# led_brick.net
KiCad netlist of a schematic drawn in EAGLE
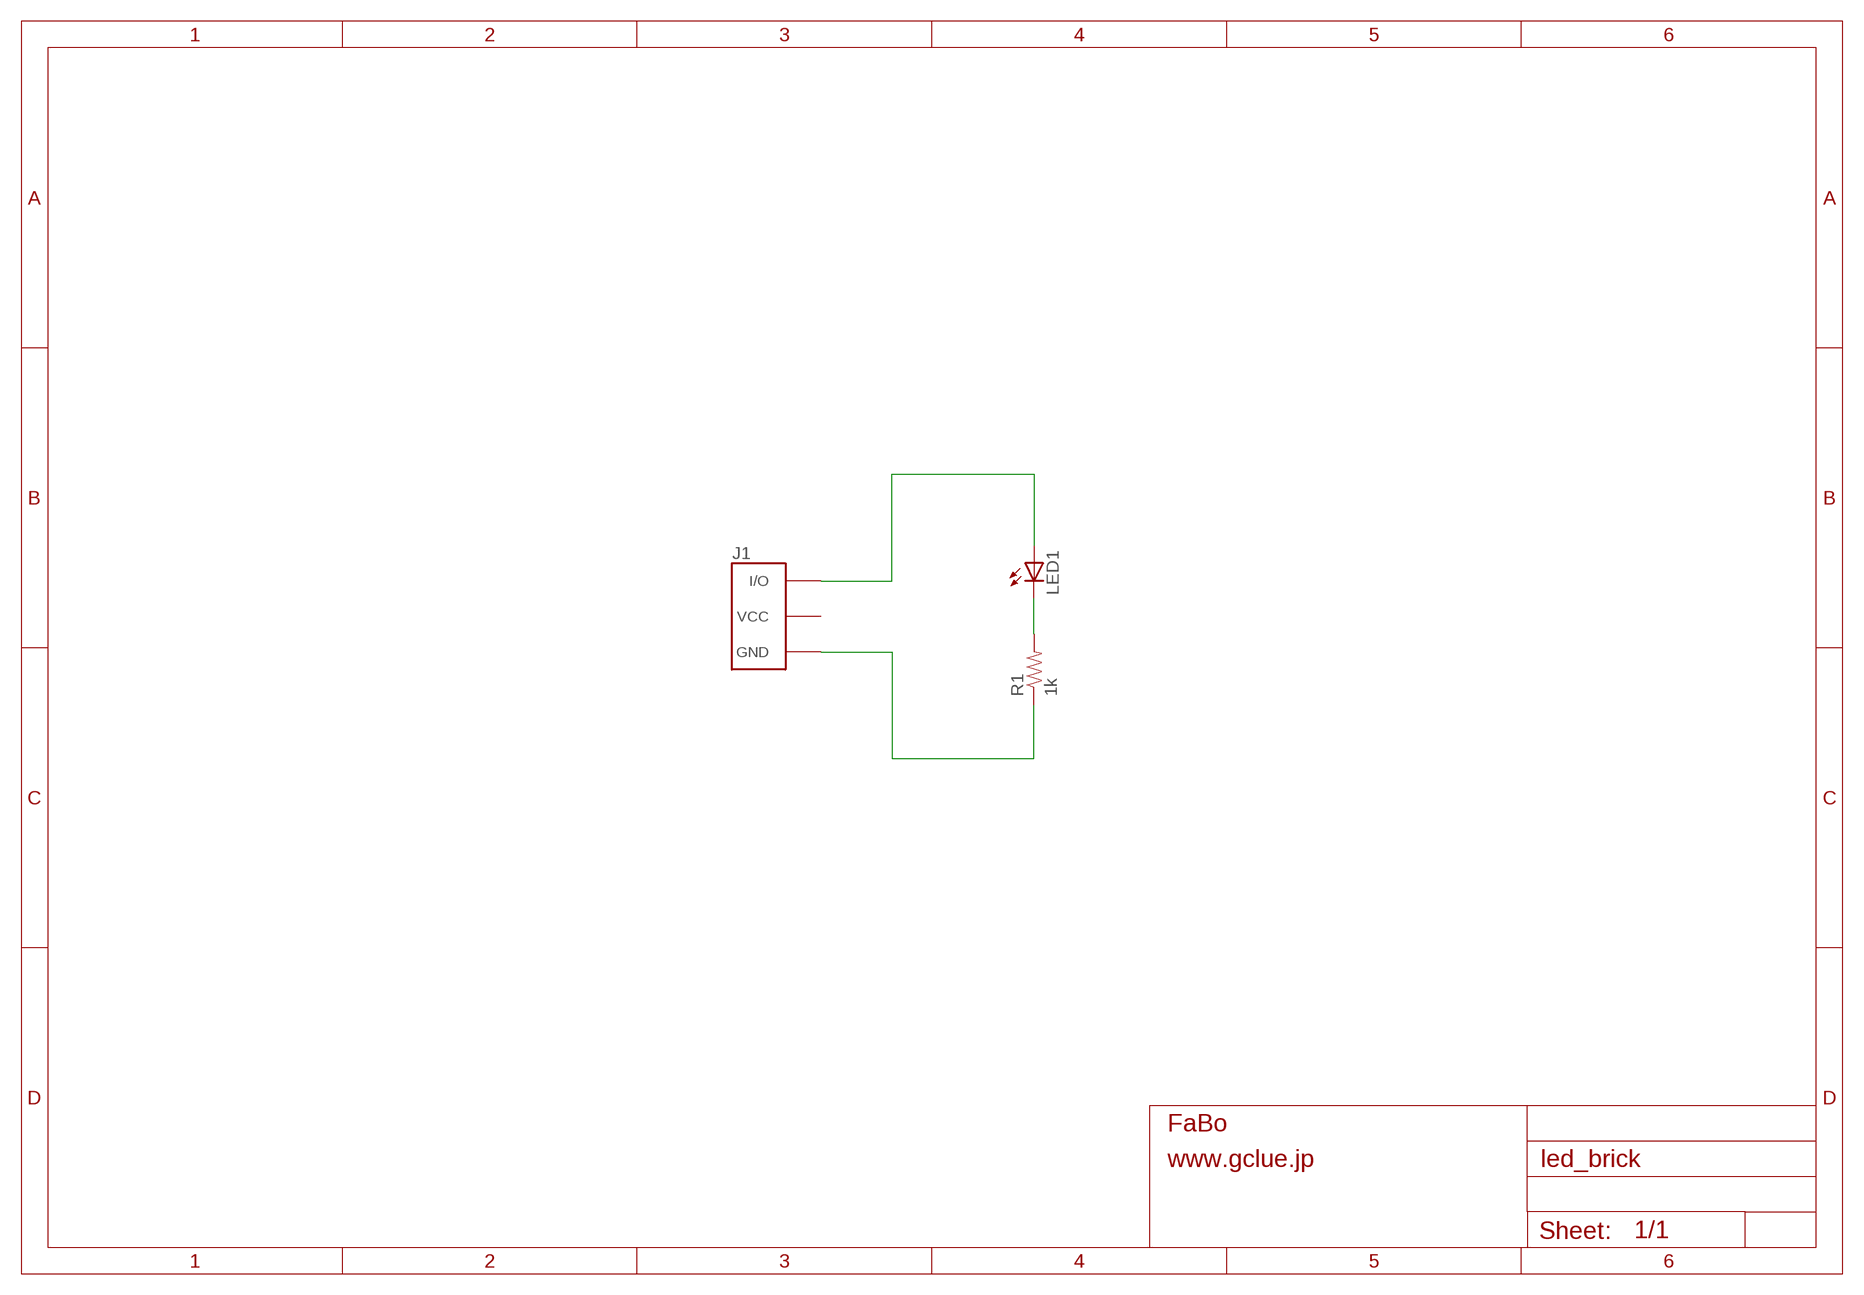
[diagram p0: schematic, sheet 1]

(export (version "E")
  (design (tool "Eeschema 10.0.6"))
  (components
    (comp (ref "J1")
      (value "BRICK_3PIN")
      (footprint "eagle-import:BRICK_3PIN")
      (libsource (lib "eagle-import") (part "BRICK_3PIN"))
    )
    (comp (ref "LED1")
      (value "LED")
      (footprint "eagle-import:LED5MM")
      (libsource (lib "eagle-import") (part "LED5MM"))
    )
    (comp (ref "R1")
      (value "1k")
      (footprint "eagle-import:AXIAL-0.4")
      (libsource (lib "eagle-import") (part "RESISTORPTH-1/4W"))
    )
  )
  (nets
    (net (code "1") (name "Net-(J1-I{slash}O)") (class "Default")
      (node (ref "J1") (pin "IN/OUT") (pinfunction "I/O_IN/OUT") (pintype "bidirectional"))
      (node (ref "LED1") (pin "A") (pinfunction "A_A") (pintype "passive"))
    )
    (net (code "2") (name "Net-(LED1-C)") (class "Default")
      (node (ref "LED1") (pin "K") (pinfunction "C_K") (pintype "passive"))
      (node (ref "R1") (pin "P$2") (pinfunction "2_P$2") (pintype "passive"))
    )
    (net (code "3") (name "Net-(R1-1)") (class "Default")
      (node (ref "J1") (pin "GND") (pinfunction "GND_GND") (pintype "bidirectional"))
      (node (ref "R1") (pin "P$1") (pinfunction "1_P$1") (pintype "passive"))
    )
    (net (code "4") (name "unconnected-(J1-PadVCC)") (class "Default")
      (node (ref "J1") (pin "VCC") (pinfunction "VCC_VCC") (pintype "bidirectional"))
    )
  )
)
